# half-pint-turbidimeter_led.net
KiCad netlist of a schematic drawn in EAGLE
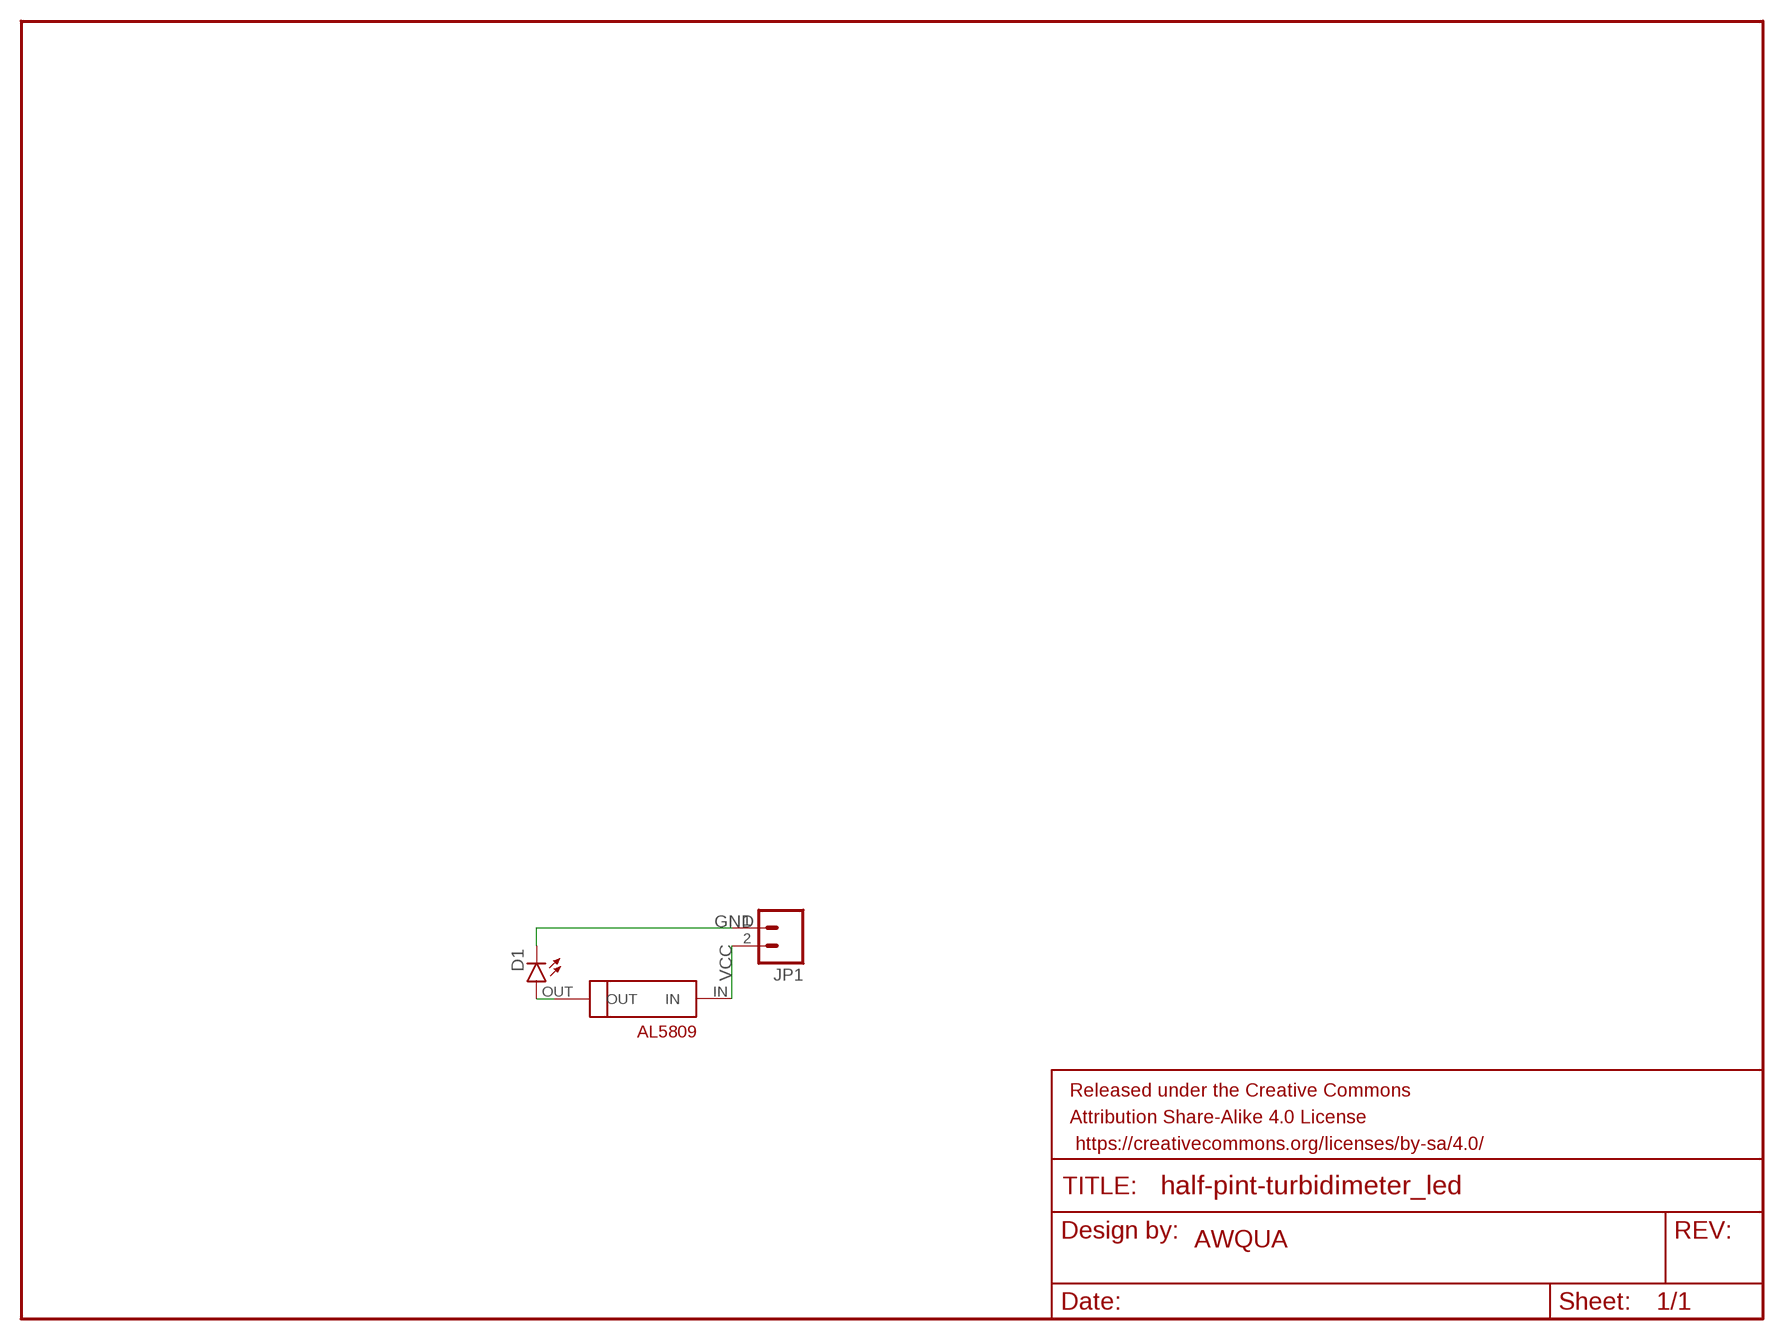
[diagram p0: schematic, sheet 1]

(export (version "E")
  (design (tool "Eeschema 10.0.6"))
  (components
    (comp (ref "D1")
      (value "LED5MM")
      (footprint "eagle-import:LED5MM")
      (libsource (lib "eagle-import") (part "LED5MM"))
    )
    (comp (ref "FRAME1")
      (value "FRAME-LETTER")
      (footprint "eagle-import:CREATIVE_COMMONS")
      (libsource (lib "eagle-import") (part "FRAME-LETTER"))
    )
    (comp (ref "JP1")
      (value "M021X02_NO_SILK")
      (footprint "eagle-import:1X02_NO_SILK")
      (libsource (lib "eagle-import") (part "M021X02_NO_SILK"))
    )
    (comp (ref "U$1")
      (value "AL5809")
      (footprint "eagle-import:AL5809")
      (libsource (lib "eagle-import") (part "AL5809"))
    )
  )
  (nets
    (net (code "1") (name "/GND") (class "Default")
      (node (ref "D1") (pin "K") (pinfunction "C_K") (pintype "passive"))
      (node (ref "JP1") (pin "1") (pinfunction "1_1") (pintype "passive"))
    )
    (net (code "2") (name "/VCC") (class "Default")
      (node (ref "JP1") (pin "2") (pinfunction "2_2") (pintype "passive"))
      (node (ref "U$1") (pin "IN") (pinfunction "IN_IN") (pintype "bidirectional"))
    )
    (net (code "3") (name "Net-(D1-PadA)") (class "Default")
      (node (ref "D1") (pin "A") (pinfunction "A_A") (pintype "passive"))
      (node (ref "U$1") (pin "OUT") (pinfunction "OUT_OUT") (pintype "bidirectional"))
    )
  )
)
